# design.net
KiCad netlist of a schematic drawn in Altium Designer
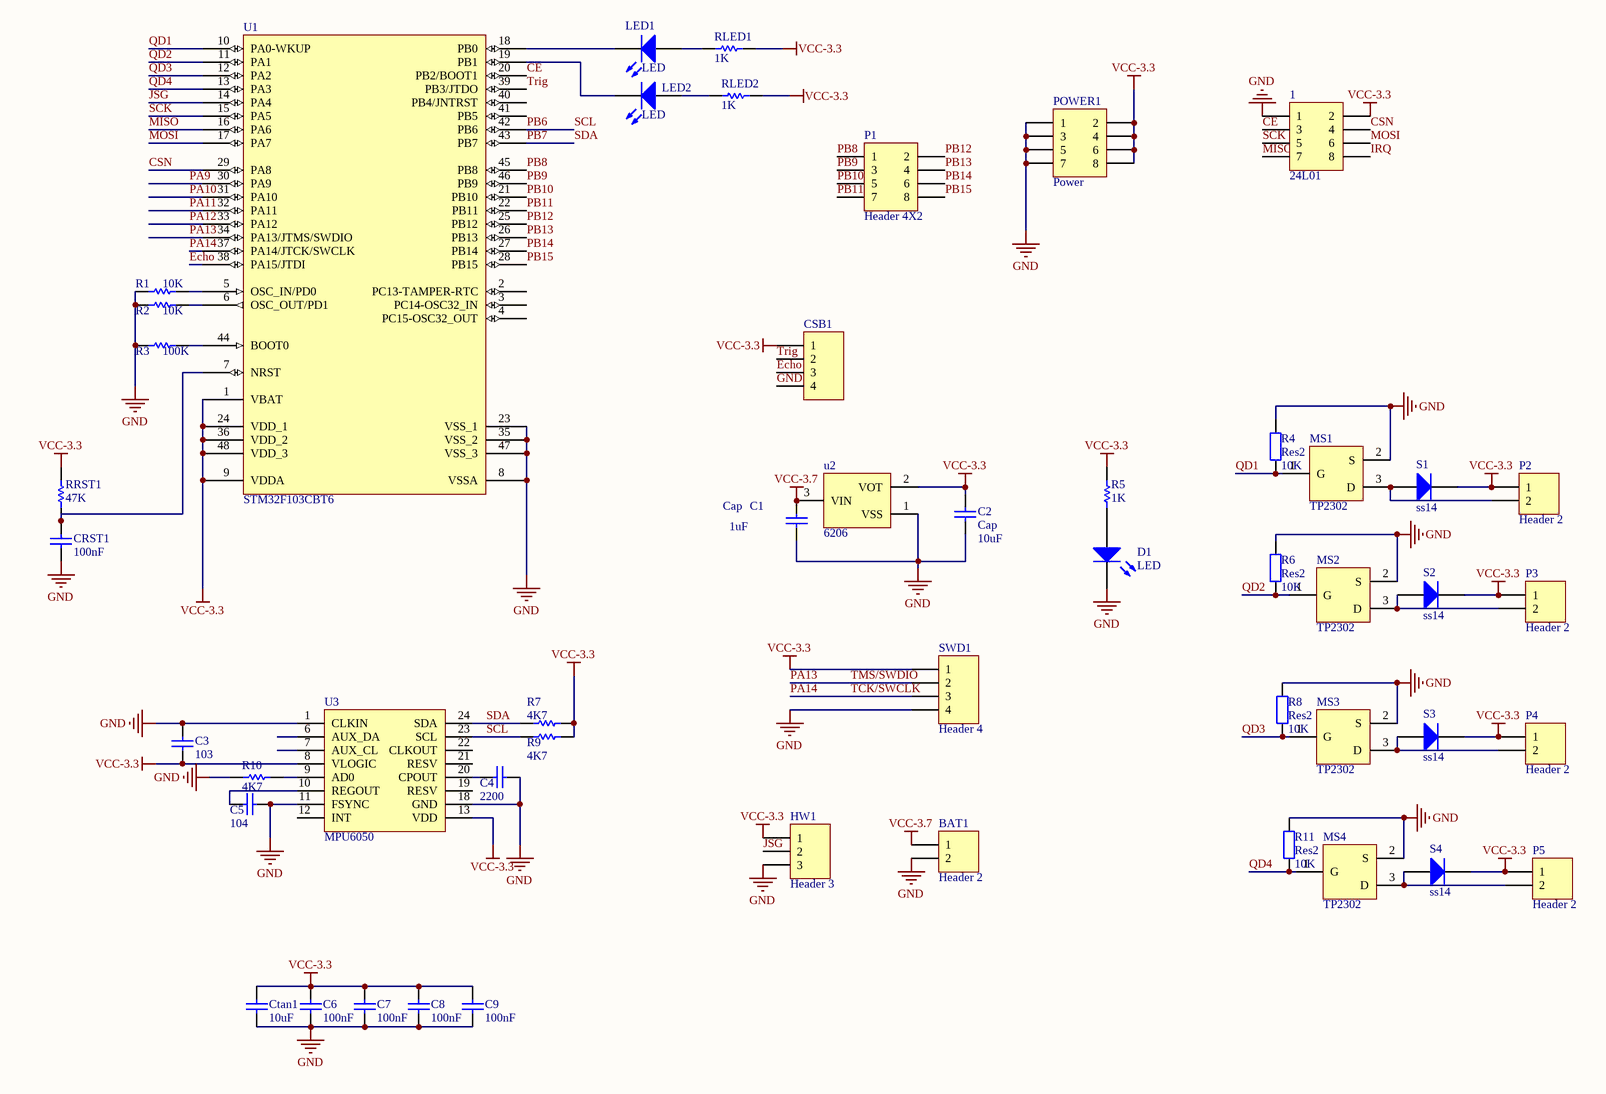
[diagram p0: 比赛飞控.SchDoc]

(export (version "E")
  (design (tool "Eeschema 10.0.6"))
  (components
    (comp (ref "1")
      (value "24L01")
      (footprint "HDR2X4")
      (description "Header, 4-Pin, Dual row")
      (fields (field (name "PUBLISHER") "Altium Limited"))
      (libsource (lib "Miscellaneous Connectors") (part "Header 4X2"))
    )
    (comp (ref "BAT1")
      (value "Header 2")
      (footprint "HDR1X2")
      (description "Header, 2-Pin")
      (fields (field (name "PUBLISHER") "Altium Limited"))
      (libsource (lib "Miscellaneous Connectors") (part "Header 2"))
    )
    (comp (ref "C1")
      (value "Cap")
      (footprint "0805")
      (description "Capacitor")
      (fields (field (name "ALTIUM_VALUE") "1uF") (field (name "PUBLISHER") "Altium Limited"))
      (libsource (lib "Miscellaneous Devices") (part "Cap"))
    )
    (comp (ref "C2")
      (value "Cap")
      (footprint "0805")
      (description "Capacitor")
      (fields (field (name "ALTIUM_VALUE") "10uF") (field (name "PUBLISHER") "Altium Limited"))
      (libsource (lib "Miscellaneous Devices") (part "Cap"))
    )
    (comp (ref "C3")
      (value "103")
      (footprint "0805")
      (description "Capacitor")
      (fields (field (name "Comment") "Cap") (field (name "PUBLISHER") "Altium Limited"))
      (libsource (lib "Miscellaneous Devices") (part "Cap"))
    )
    (comp (ref "C4")
      (value "2200")
      (footprint "0805")
      (description "Capacitor")
      (fields (field (name "Comment") "Cap") (field (name "PUBLISHER") "Altium Limited"))
      (libsource (lib "Miscellaneous Devices") (part "Cap"))
    )
    (comp (ref "C5")
      (value "104")
      (footprint "0805")
      (description "Capacitor")
      (fields (field (name "Comment") "Cap") (field (name "PUBLISHER") "Altium Limited"))
      (libsource (lib "Miscellaneous Devices") (part "Cap"))
    )
    (comp (ref "C6")
      (value "100nF")
      (footprint "0805")
      (description "Capacitor")
      (fields (field (name "Comment") "Cap") (field (name "PUBLISHER") "Altium Limited"))
      (libsource (lib "Miscellaneous Devices") (part "Cap"))
    )
    (comp (ref "C7")
      (value "100nF")
      (footprint "0805")
      (description "Capacitor")
      (fields (field (name "Comment") "Cap") (field (name "PUBLISHER") "Altium Limited"))
      (libsource (lib "Miscellaneous Devices") (part "Cap"))
    )
    (comp (ref "C8")
      (value "100nF")
      (footprint "0805")
      (description "Capacitor")
      (fields (field (name "Comment") "Cap") (field (name "PUBLISHER") "Altium Limited"))
      (libsource (lib "Miscellaneous Devices") (part "Cap"))
    )
    (comp (ref "C9")
      (value "100nF")
      (footprint "0805")
      (description "Capacitor")
      (fields (field (name "Comment") "Cap") (field (name "PUBLISHER") "Altium Limited"))
      (libsource (lib "Miscellaneous Devices") (part "Cap"))
    )
    (comp (ref "CRST1")
      (value "100nF")
      (footprint "0805")
      (description "Capacitor")
      (fields (field (name "Comment") "Cap") (field (name "PUBLISHER") "Altium Limited"))
      (libsource (lib "Miscellaneous Devices") (part "Cap"))
    )
    (comp (ref "CSB1")
      (value "~")
      (footprint "HDR1X4")
      (description "Header, 4-Pin")
      (fields (field (name "PUBLISHER") "Altium Limited"))
      (libsource (lib "Miscellaneous Connectors") (part "Header 4"))
    )
    (comp (ref "Ctan1")
      (value "10uF")
      (footprint "0805")
      (description "Capacitor")
      (fields (field (name "Comment") "Cap") (field (name "PUBLISHER") "Altium Limited"))
      (libsource (lib "Miscellaneous Devices") (part "Cap"))
    )
    (comp (ref "D1")
      (value "LED")
      (footprint "0805")
      (description "Typical BLUE SiC LED")
      (fields (field (name "PUBLISHER") "Altium Limited"))
      (libsource (lib "Miscellaneous Devices") (part "LED3"))
    )
    (comp (ref "HW1")
      (value "Header 3")
      (footprint "HDR1X3")
      (description "Header, 3-Pin")
      (fields (field (name "PUBLISHER") "Altium Limited"))
      (libsource (lib "Miscellaneous Connectors") (part "Header 3"))
    )
    (comp (ref "LED1")
      (value "LED")
      (footprint "0805")
      (description "Typical BLUE SiC LED")
      (fields (field (name "PUBLISHER") "Altium Limited"))
      (libsource (lib "Miscellaneous Devices") (part "LED3"))
    )
    (comp (ref "LED2")
      (value "LED")
      (footprint "0805")
      (description "Typical BLUE SiC LED")
      (fields (field (name "PUBLISHER") "Altium Limited"))
      (libsource (lib "Miscellaneous Devices") (part "LED3"))
    )
    (comp (ref "MS1") (value "TP2302") (footprint "SOT-23") (libsource (lib "TP2302") (part "TP2302")))
    (comp (ref "MS2") (value "TP2302") (footprint "SOT-23") (libsource (lib "TP2302") (part "TP2302")))
    (comp (ref "MS3") (value "TP2302") (footprint "SOT-23") (libsource (lib "TP2302") (part "TP2302")))
    (comp (ref "MS4") (value "TP2302") (footprint "SOT-23") (libsource (lib "TP2302") (part "TP2302")))
    (comp (ref "P1")
      (value "Header 4X2")
      (footprint "HDR2X4")
      (description "Header, 4-Pin, Dual row")
      (fields (field (name "PUBLISHER") "Altium Limited"))
      (libsource (lib "Miscellaneous Connectors") (part "Header 4X2"))
    )
    (comp (ref "P2")
      (value "Header 2")
      (footprint "HDR1X2")
      (description "Header, 2-Pin")
      (fields (field (name "PUBLISHER") "Altium Limited"))
      (libsource (lib "Miscellaneous Connectors") (part "Header 2"))
    )
    (comp (ref "P3")
      (value "Header 2")
      (footprint "HDR1X2")
      (description "Header, 2-Pin")
      (fields (field (name "PUBLISHER") "Altium Limited"))
      (libsource (lib "Miscellaneous Connectors") (part "Header 2"))
    )
    (comp (ref "P4")
      (value "Header 2")
      (footprint "HDR1X2")
      (description "Header, 2-Pin")
      (fields (field (name "PUBLISHER") "Altium Limited"))
      (libsource (lib "Miscellaneous Connectors") (part "Header 2"))
    )
    (comp (ref "P5")
      (value "Header 2")
      (footprint "HDR1X2")
      (description "Header, 2-Pin")
      (fields (field (name "PUBLISHER") "Altium Limited"))
      (libsource (lib "Miscellaneous Connectors") (part "Header 2"))
    )
    (comp (ref "POWER1")
      (value "Power")
      (footprint "HDR2X4")
      (description "Header, 4-Pin, Dual row")
      (fields (field (name "PUBLISHER") "Altium Limited"))
      (libsource (lib "Miscellaneous Connectors") (part "Header 4X2"))
    )
    (comp (ref "R1")
      (value "10K")
      (footprint "0603")
      (description "Resistor")
      (fields (field (name "Comment") "Res1") (field (name "PUBLISHER") "Altium Limited"))
      (libsource (lib "Miscellaneous Devices") (part "Res1"))
    )
    (comp (ref "R2")
      (value "10K")
      (footprint "0603")
      (description "Resistor")
      (fields (field (name "Comment") "Res1") (field (name "PUBLISHER") "Altium Limited"))
      (libsource (lib "Miscellaneous Devices") (part "Res1"))
    )
    (comp (ref "R3")
      (value "100K")
      (footprint "0603")
      (description "Resistor")
      (fields (field (name "Comment") "Res1") (field (name "PUBLISHER") "Altium Limited"))
      (libsource (lib "Miscellaneous Devices") (part "Res1"))
    )
    (comp (ref "R4")
      (value "Res2")
      (footprint "0805")
      (description "Resistor")
      (fields (field (name "ALTIUM_VALUE") "10K") (field (name "PUBLISHER") "Altium Limited"))
      (libsource (lib "Miscellaneous Devices") (part "Res2"))
    )
    (comp (ref "R5")
      (value "1K")
      (footprint "0805")
      (description "Resistor")
      (fields (field (name "Comment") "Res1") (field (name "PUBLISHER") "Altium Limited"))
      (libsource (lib "Miscellaneous Devices") (part "Res1"))
    )
    (comp (ref "R6")
      (value "Res2")
      (footprint "0805")
      (description "Resistor")
      (fields (field (name "ALTIUM_VALUE") "10K") (field (name "PUBLISHER") "Altium Limited"))
      (libsource (lib "Miscellaneous Devices") (part "Res2"))
    )
    (comp (ref "R7")
      (value "4K7")
      (footprint "0805")
      (description "Resistor")
      (fields (field (name "Comment") "Res1") (field (name "PUBLISHER") "Altium Limited"))
      (libsource (lib "Miscellaneous Devices") (part "Res1"))
    )
    (comp (ref "R8")
      (value "Res2")
      (footprint "0805")
      (description "Resistor")
      (fields (field (name "ALTIUM_VALUE") "10K") (field (name "PUBLISHER") "Altium Limited"))
      (libsource (lib "Miscellaneous Devices") (part "Res2"))
    )
    (comp (ref "R9")
      (value "4K7")
      (footprint "0805")
      (description "Resistor")
      (fields (field (name "Comment") "Res1") (field (name "PUBLISHER") "Altium Limited"))
      (libsource (lib "Miscellaneous Devices") (part "Res1"))
    )
    (comp (ref "R10")
      (value "4K7")
      (footprint "0805")
      (description "Resistor")
      (fields (field (name "Comment") "Res1") (field (name "PUBLISHER") "Altium Limited"))
      (libsource (lib "Miscellaneous Devices") (part "Res1"))
    )
    (comp (ref "R11")
      (value "Res2")
      (footprint "0805")
      (description "Resistor")
      (fields (field (name "ALTIUM_VALUE") "10K") (field (name "PUBLISHER") "Altium Limited"))
      (libsource (lib "Miscellaneous Devices") (part "Res2"))
    )
    (comp (ref "RLED1")
      (value "1K")
      (footprint "0805")
      (description "Resistor")
      (fields (field (name "Comment") "Res1") (field (name "PUBLISHER") "Altium Limited"))
      (libsource (lib "Miscellaneous Devices") (part "Res1"))
    )
    (comp (ref "RLED2")
      (value "1K")
      (footprint "0805")
      (description "Resistor")
      (fields (field (name "Comment") "Res1") (field (name "PUBLISHER") "Altium Limited"))
      (libsource (lib "Miscellaneous Devices") (part "Res1"))
    )
    (comp (ref "RRST1")
      (value "47K")
      (footprint "0805")
      (description "Resistor")
      (fields (field (name "Comment") "Res1") (field (name "PUBLISHER") "Altium Limited"))
      (libsource (lib "Miscellaneous Devices") (part "Res1"))
    )
    (comp (ref "S1")
      (value "ss14")
      (footprint "SOD-323")
      (description "3 Amp General Purpose Rectifier")
      (fields (field (name "PUBLISHER") "Altium Limited"))
      (libsource (lib "Miscellaneous Devices") (part "Diode 1N5406"))
    )
    (comp (ref "S2")
      (value "ss14")
      (footprint "SOD-323")
      (description "3 Amp General Purpose Rectifier")
      (fields (field (name "PUBLISHER") "Altium Limited"))
      (libsource (lib "Miscellaneous Devices") (part "Diode 1N5406"))
    )
    (comp (ref "S3")
      (value "ss14")
      (footprint "SOD-323")
      (description "3 Amp General Purpose Rectifier")
      (fields (field (name "PUBLISHER") "Altium Limited"))
      (libsource (lib "Miscellaneous Devices") (part "Diode 1N5406"))
    )
    (comp (ref "S4")
      (value "ss14")
      (footprint "SOD-323")
      (description "3 Amp General Purpose Rectifier")
      (fields (field (name "PUBLISHER") "Altium Limited"))
      (libsource (lib "Miscellaneous Devices") (part "Diode 1N5406"))
    )
    (comp (ref "SWD1")
      (value "Header 4")
      (footprint "HDR1X4")
      (description "Header, 4-Pin")
      (fields (field (name "PUBLISHER") "Altium Limited"))
      (libsource (lib "Miscellaneous Connectors") (part "Header 4"))
    )
    (comp (ref "U1")
      (value "STM32F103CBT6")
      (footprint "LQFP48_N")
      (description "STM32 ARM-based 32-bit MCU with 128 Kbytes Flash, 48-pin LQFP, Industrial Temperature")
      (fields (field (name "PUBLISHER") "Altium Limited"))
      (libsource (lib "ST Microcontroller 32-Bit STM32") (part "STM32F103CBT6"))
    )
    (comp (ref "u2") (value "6206") (footprint "SOT346-3AN") (libsource (lib "6206") (part "6206")))
    (comp (ref "U3")
      (value "MPU6050")
      (footprint "QFN-24")
      (description "Hex-Axis Sensor")
      (libsource (lib "My") (part "MPU6050"))
    )
  )
  (nets
    (net (code "1") (name "/CE") (class "Default")
      (node (ref "1") (pin "3") (pinfunction "3_3") (pintype "passive"))
      (node (ref "U1") (pin "20") (pinfunction "PB2/BOOT1_20") (pintype "bidirectional"))
    )
    (net (code "2") (name "/CSN") (class "Default")
      (node (ref "1") (pin "4") (pinfunction "4_4") (pintype "passive"))
      (node (ref "U1") (pin "29") (pinfunction "PA8_29") (pintype "bidirectional"))
    )
    (net (code "3") (name "/Echo") (class "Default")
      (node (ref "CSB1") (pin "3") (pinfunction "3_3") (pintype "passive"))
      (node (ref "U1") (pin "38") (pinfunction "PA15/JTDI_38") (pintype "bidirectional"))
    )
    (net (code "4") (name "/IRQ") (class "Default")
      (node (ref "1") (pin "8") (pinfunction "8_8") (pintype "passive"))
    )
    (net (code "5") (name "/JSG") (class "Default")
      (node (ref "HW1") (pin "2") (pinfunction "2_2") (pintype "passive"))
      (node (ref "U1") (pin "14") (pinfunction "PA4_14") (pintype "bidirectional"))
    )
    (net (code "6") (name "/MISO") (class "Default")
      (node (ref "1") (pin "7") (pinfunction "7_7") (pintype "passive"))
      (node (ref "U1") (pin "16") (pinfunction "PA6_16") (pintype "bidirectional"))
    )
    (net (code "7") (name "/MOSI") (class "Default")
      (node (ref "1") (pin "6") (pinfunction "6_6") (pintype "passive"))
      (node (ref "U1") (pin "17") (pinfunction "PA7_17") (pintype "bidirectional"))
    )
    (net (code "8") (name "/PA9") (class "Default")
      (node (ref "U1") (pin "30") (pinfunction "PA9_30") (pintype "bidirectional"))
    )
    (net (code "9") (name "/PA10") (class "Default")
      (node (ref "U1") (pin "31") (pinfunction "PA10_31") (pintype "bidirectional"))
    )
    (net (code "10") (name "/PA11") (class "Default")
      (node (ref "U1") (pin "32") (pinfunction "PA11_32") (pintype "bidirectional"))
    )
    (net (code "11") (name "/PA12") (class "Default")
      (node (ref "U1") (pin "33") (pinfunction "PA12_33") (pintype "bidirectional"))
    )
    (net (code "12") (name "/PA13") (class "Default")
      (node (ref "SWD1") (pin "2") (pinfunction "2_2") (pintype "passive"))
      (node (ref "U1") (pin "34") (pinfunction "PA13/JTMS/SWDIO_34") (pintype "bidirectional"))
    )
    (net (code "13") (name "/PA14") (class "Default")
      (node (ref "SWD1") (pin "3") (pinfunction "3_3") (pintype "passive"))
      (node (ref "U1") (pin "37") (pinfunction "PA14/JTCK/SWCLK_37") (pintype "bidirectional"))
    )
    (net (code "14") (name "/PB6") (class "Default")
      (node (ref "R9") (pin "1") (pinfunction "1_1") (pintype "passive"))
      (node (ref "U1") (pin "42") (pinfunction "PB6_42") (pintype "bidirectional"))
      (node (ref "U3") (pin "23") (pinfunction "SCL_23") (pintype "passive"))
    )
    (net (code "15") (name "/PB7") (class "Default")
      (node (ref "R7") (pin "1") (pinfunction "1_1") (pintype "passive"))
      (node (ref "U1") (pin "43") (pinfunction "PB7_43") (pintype "bidirectional"))
      (node (ref "U3") (pin "24") (pinfunction "SDA_24") (pintype "passive"))
    )
    (net (code "16") (name "/PB8") (class "Default")
      (node (ref "P1") (pin "1") (pinfunction "1_1") (pintype "passive"))
      (node (ref "U1") (pin "45") (pinfunction "PB8_45") (pintype "bidirectional"))
    )
    (net (code "17") (name "/PB9") (class "Default")
      (node (ref "P1") (pin "3") (pinfunction "3_3") (pintype "passive"))
      (node (ref "U1") (pin "46") (pinfunction "PB9_46") (pintype "bidirectional"))
    )
    (net (code "18") (name "/PB10") (class "Default")
      (node (ref "P1") (pin "5") (pinfunction "5_5") (pintype "passive"))
      (node (ref "U1") (pin "21") (pinfunction "PB10_21") (pintype "bidirectional"))
    )
    (net (code "19") (name "/PB11") (class "Default")
      (node (ref "P1") (pin "7") (pinfunction "7_7") (pintype "passive"))
      (node (ref "U1") (pin "22") (pinfunction "PB11_22") (pintype "bidirectional"))
    )
    (net (code "20") (name "/PB12") (class "Default")
      (node (ref "P1") (pin "2") (pinfunction "2_2") (pintype "passive"))
      (node (ref "U1") (pin "25") (pinfunction "PB12_25") (pintype "bidirectional"))
    )
    (net (code "21") (name "/PB13") (class "Default")
      (node (ref "P1") (pin "4") (pinfunction "4_4") (pintype "passive"))
      (node (ref "U1") (pin "26") (pinfunction "PB13_26") (pintype "bidirectional"))
    )
    (net (code "22") (name "/PB14") (class "Default")
      (node (ref "P1") (pin "6") (pinfunction "6_6") (pintype "passive"))
      (node (ref "U1") (pin "27") (pinfunction "PB14_27") (pintype "bidirectional"))
    )
    (net (code "23") (name "/PB15") (class "Default")
      (node (ref "P1") (pin "8") (pinfunction "8_8") (pintype "passive"))
      (node (ref "U1") (pin "28") (pinfunction "PB15_28") (pintype "bidirectional"))
    )
    (net (code "24") (name "/QD1") (class "Default")
      (node (ref "MS1") (pin "1") (pinfunction "G_1") (pintype "passive"))
      (node (ref "R4") (pin "1") (pinfunction "1_1") (pintype "passive"))
      (node (ref "U1") (pin "10") (pinfunction "PA0-WKUP_10") (pintype "bidirectional"))
    )
    (net (code "25") (name "/QD2") (class "Default")
      (node (ref "MS2") (pin "1") (pinfunction "G_1") (pintype "passive"))
      (node (ref "R6") (pin "1") (pinfunction "1_1") (pintype "passive"))
      (node (ref "U1") (pin "11") (pinfunction "PA1_11") (pintype "bidirectional"))
    )
    (net (code "26") (name "/QD3") (class "Default")
      (node (ref "MS3") (pin "1") (pinfunction "G_1") (pintype "passive"))
      (node (ref "R8") (pin "1") (pinfunction "1_1") (pintype "passive"))
      (node (ref "U1") (pin "12") (pinfunction "PA2_12") (pintype "bidirectional"))
    )
    (net (code "27") (name "/QD4") (class "Default")
      (node (ref "MS4") (pin "1") (pinfunction "G_1") (pintype "passive"))
      (node (ref "R11") (pin "1") (pinfunction "1_1") (pintype "passive"))
      (node (ref "U1") (pin "13") (pinfunction "PA3_13") (pintype "bidirectional"))
    )
    (net (code "28") (name "/SCK") (class "Default")
      (node (ref "1") (pin "5") (pinfunction "5_5") (pintype "passive"))
      (node (ref "U1") (pin "15") (pinfunction "PA5_15") (pintype "bidirectional"))
    )
    (net (code "29") (name "/Trig") (class "Default")
      (node (ref "CSB1") (pin "2") (pinfunction "2_2") (pintype "passive"))
      (node (ref "U1") (pin "39") (pinfunction "PB3/JTDO_39") (pintype "bidirectional"))
    )
    (net (code "30") (name "GND") (class "Default")
      (node (ref "1") (pin "1") (pinfunction "1_1") (pintype "passive"))
      (node (ref "BAT1") (pin "2") (pinfunction "2_2") (pintype "passive"))
      (node (ref "C1") (pin "2") (pinfunction "2_2") (pintype "passive"))
      (node (ref "C2") (pin "2") (pinfunction "2_2") (pintype "passive"))
      (node (ref "C3") (pin "2") (pinfunction "2_2") (pintype "passive"))
      (node (ref "C4") (pin "2") (pinfunction "2_2") (pintype "passive"))
      (node (ref "C5") (pin "1") (pinfunction "1_1") (pintype "passive"))
      (node (ref "C6") (pin "1") (pinfunction "1_1") (pintype "passive"))
      (node (ref "C7") (pin "1") (pinfunction "1_1") (pintype "passive"))
      (node (ref "C8") (pin "1") (pinfunction "1_1") (pintype "passive"))
      (node (ref "C9") (pin "1") (pinfunction "1_1") (pintype "passive"))
      (node (ref "CRST1") (pin "2") (pinfunction "2_2") (pintype "passive"))
      (node (ref "CSB1") (pin "4") (pinfunction "4_4") (pintype "passive"))
      (node (ref "Ctan1") (pin "1") (pinfunction "1_1") (pintype "passive"))
      (node (ref "D1") (pin "2") (pinfunction "K_2") (pintype "passive"))
      (node (ref "HW1") (pin "3") (pinfunction "3_3") (pintype "passive"))
      (node (ref "MS1") (pin "2") (pinfunction "S_2") (pintype "passive"))
      (node (ref "MS2") (pin "2") (pinfunction "S_2") (pintype "passive"))
      (node (ref "MS3") (pin "2") (pinfunction "S_2") (pintype "passive"))
      (node (ref "MS4") (pin "2") (pinfunction "S_2") (pintype "passive"))
      (node (ref "POWER1") (pin "1") (pinfunction "1_1") (pintype "passive"))
      (node (ref "POWER1") (pin "3") (pinfunction "3_3") (pintype "passive"))
      (node (ref "POWER1") (pin "5") (pinfunction "5_5") (pintype "passive"))
      (node (ref "POWER1") (pin "7") (pinfunction "7_7") (pintype "passive"))
      (node (ref "R1") (pin "1") (pinfunction "1_1") (pintype "passive"))
      (node (ref "R10") (pin "1") (pinfunction "1_1") (pintype "passive"))
      (node (ref "R11") (pin "2") (pinfunction "2_2") (pintype "passive"))
      (node (ref "R2") (pin "1") (pinfunction "1_1") (pintype "passive"))
      (node (ref "R3") (pin "1") (pinfunction "1_1") (pintype "passive"))
      (node (ref "R4") (pin "2") (pinfunction "2_2") (pintype "passive"))
      (node (ref "R6") (pin "2") (pinfunction "2_2") (pintype "passive"))
      (node (ref "R8") (pin "2") (pinfunction "2_2") (pintype "passive"))
      (node (ref "SWD1") (pin "4") (pinfunction "4_4") (pintype "passive"))
      (node (ref "U1") (pin "23") (pinfunction "VSS_1_23") (pintype "power_in"))
      (node (ref "U1") (pin "35") (pinfunction "VSS_2_35") (pintype "power_in"))
      (node (ref "U1") (pin "47") (pinfunction "VSS_3_47") (pintype "power_in"))
      (node (ref "U1") (pin "8") (pinfunction "VSSA_8") (pintype "power_in"))
      (node (ref "U3") (pin "1") (pinfunction "CLKIN_1") (pintype "passive"))
      (node (ref "U3") (pin "11") (pinfunction "FSYNC_11") (pintype "passive"))
      (node (ref "U3") (pin "18") (pinfunction "GND_18") (pintype "passive"))
      (node (ref "u2") (pin "1") (pinfunction "VSS_1") (pintype "passive"))
    )
    (net (code "31") (name "Net-(D1-A)") (class "Default")
      (node (ref "D1") (pin "1") (pinfunction "A_1") (pintype "passive"))
      (node (ref "R5") (pin "1") (pinfunction "1_1") (pintype "passive"))
    )
    (net (code "32") (name "Net-(LED1-A)") (class "Default")
      (node (ref "LED1") (pin "1") (pinfunction "A_1") (pintype "passive"))
      (node (ref "RLED1") (pin "2") (pinfunction "2_2") (pintype "passive"))
    )
    (net (code "33") (name "Net-(LED1-K)") (class "Default")
      (node (ref "LED1") (pin "2") (pinfunction "K_2") (pintype "passive"))
      (node (ref "U1") (pin "18") (pinfunction "PB0_18") (pintype "bidirectional"))
    )
    (net (code "34") (name "Net-(LED2-A)") (class "Default")
      (node (ref "LED2") (pin "1") (pinfunction "A_1") (pintype "passive"))
      (node (ref "RLED2") (pin "2") (pinfunction "2_2") (pintype "passive"))
    )
    (net (code "35") (name "Net-(LED2-K)") (class "Default")
      (node (ref "LED2") (pin "2") (pinfunction "K_2") (pintype "passive"))
      (node (ref "U1") (pin "19") (pinfunction "PB1_19") (pintype "bidirectional"))
    )
    (net (code "36") (name "Net-(MS1-D)") (class "Default")
      (node (ref "MS1") (pin "3") (pinfunction "D_3") (pintype "passive"))
      (node (ref "P2") (pin "2") (pinfunction "2_2") (pintype "passive"))
      (node (ref "S1") (pin "1") (pinfunction "A_1") (pintype "passive"))
    )
    (net (code "37") (name "Net-(MS2-D)") (class "Default")
      (node (ref "MS2") (pin "3") (pinfunction "D_3") (pintype "passive"))
      (node (ref "P3") (pin "2") (pinfunction "2_2") (pintype "passive"))
      (node (ref "S2") (pin "1") (pinfunction "A_1") (pintype "passive"))
    )
    (net (code "38") (name "Net-(MS3-D)") (class "Default")
      (node (ref "MS3") (pin "3") (pinfunction "D_3") (pintype "passive"))
      (node (ref "P4") (pin "2") (pinfunction "2_2") (pintype "passive"))
      (node (ref "S3") (pin "1") (pinfunction "A_1") (pintype "passive"))
    )
    (net (code "39") (name "Net-(MS4-D)") (class "Default")
      (node (ref "MS4") (pin "3") (pinfunction "D_3") (pintype "passive"))
      (node (ref "P5") (pin "2") (pinfunction "2_2") (pintype "passive"))
      (node (ref "S4") (pin "1") (pinfunction "A_1") (pintype "passive"))
    )
    (net (code "40") (name "Net-(U1-BOOT0)") (class "Default")
      (node (ref "R3") (pin "2") (pinfunction "2_2") (pintype "passive"))
      (node (ref "U1") (pin "44") (pinfunction "BOOT0_44") (pintype "input"))
    )
    (net (code "41") (name "Net-(U1-NRST)") (class "Default")
      (node (ref "CRST1") (pin "1") (pinfunction "1_1") (pintype "passive"))
      (node (ref "RRST1") (pin "1") (pinfunction "1_1") (pintype "passive"))
      (node (ref "U1") (pin "7") (pinfunction "NRST_7") (pintype "bidirectional"))
    )
    (net (code "42") (name "Net-(U1-OSC_IN{slash}PD0)") (class "Default")
      (node (ref "R1") (pin "2") (pinfunction "2_2") (pintype "passive"))
      (node (ref "U1") (pin "5") (pinfunction "OSC_IN/PD0_5") (pintype "input"))
    )
    (net (code "43") (name "Net-(U1-OSC_OUT{slash}PD1)") (class "Default")
      (node (ref "R2") (pin "2") (pinfunction "2_2") (pintype "passive"))
      (node (ref "U1") (pin "6") (pinfunction "OSC_OUT/PD1_6") (pintype "output"))
    )
    (net (code "44") (name "Net-(U3-AD0)") (class "Default")
      (node (ref "R10") (pin "2") (pinfunction "2_2") (pintype "passive"))
      (node (ref "U3") (pin "9") (pinfunction "AD0_9") (pintype "passive"))
    )
    (net (code "45") (name "Net-(U3-CPOUT)") (class "Default")
      (node (ref "C4") (pin "1") (pinfunction "1_1") (pintype "passive"))
      (node (ref "U3") (pin "20") (pinfunction "CPOUT_20") (pintype "passive"))
    )
    (net (code "46") (name "Net-(U3-REGOUT)") (class "Default")
      (node (ref "C5") (pin "2") (pinfunction "2_2") (pintype "passive"))
      (node (ref "U3") (pin "10") (pinfunction "REGOUT_10") (pintype "passive"))
    )
    (net (code "47") (name "VCC-3.3") (class "Default")
      (node (ref "1") (pin "2") (pinfunction "2_2") (pintype "passive"))
      (node (ref "C2") (pin "1") (pinfunction "1_1") (pintype "passive"))
      (node (ref "C3") (pin "1") (pinfunction "1_1") (pintype "passive"))
      (node (ref "C6") (pin "2") (pinfunction "2_2") (pintype "passive"))
      (node (ref "C7") (pin "2") (pinfunction "2_2") (pintype "passive"))
      (node (ref "C8") (pin "2") (pinfunction "2_2") (pintype "passive"))
      (node (ref "C9") (pin "2") (pinfunction "2_2") (pintype "passive"))
      (node (ref "CSB1") (pin "1") (pinfunction "1_1") (pintype "passive"))
      (node (ref "Ctan1") (pin "2") (pinfunction "2_2") (pintype "passive"))
      (node (ref "HW1") (pin "1") (pinfunction "1_1") (pintype "passive"))
      (node (ref "P2") (pin "1") (pinfunction "1_1") (pintype "passive"))
      (node (ref "P3") (pin "1") (pinfunction "1_1") (pintype "passive"))
      (node (ref "P4") (pin "1") (pinfunction "1_1") (pintype "passive"))
      (node (ref "P5") (pin "1") (pinfunction "1_1") (pintype "passive"))
      (node (ref "POWER1") (pin "2") (pinfunction "2_2") (pintype "passive"))
      (node (ref "POWER1") (pin "4") (pinfunction "4_4") (pintype "passive"))
      (node (ref "POWER1") (pin "6") (pinfunction "6_6") (pintype "passive"))
      (node (ref "POWER1") (pin "8") (pinfunction "8_8") (pintype "passive"))
      (node (ref "R5") (pin "2") (pinfunction "2_2") (pintype "passive"))
      (node (ref "R7") (pin "2") (pinfunction "2_2") (pintype "passive"))
      (node (ref "R9") (pin "2") (pinfunction "2_2") (pintype "passive"))
      (node (ref "RLED1") (pin "1") (pinfunction "1_1") (pintype "passive"))
      (node (ref "RLED2") (pin "1") (pinfunction "1_1") (pintype "passive"))
      (node (ref "RRST1") (pin "2") (pinfunction "2_2") (pintype "passive"))
      (node (ref "S1") (pin "2") (pinfunction "K_2") (pintype "passive"))
      (node (ref "S2") (pin "2") (pinfunction "K_2") (pintype "passive"))
      (node (ref "S3") (pin "2") (pinfunction "K_2") (pintype "passive"))
      (node (ref "S4") (pin "2") (pinfunction "K_2") (pintype "passive"))
      (node (ref "SWD1") (pin "1") (pinfunction "1_1") (pintype "passive"))
      (node (ref "U1") (pin "1") (pinfunction "VBAT_1") (pintype "power_in"))
      (node (ref "U1") (pin "24") (pinfunction "VDD_1_24") (pintype "power_in"))
      (node (ref "U1") (pin "36") (pinfunction "VDD_2_36") (pintype "power_in"))
      (node (ref "U1") (pin "48") (pinfunction "VDD_3_48") (pintype "power_in"))
      (node (ref "U1") (pin "9") (pinfunction "VDDA_9") (pintype "power_in"))
      (node (ref "U3") (pin "13") (pinfunction "VDD_13") (pintype "passive"))
      (node (ref "U3") (pin "8") (pinfunction "VLOGIC_8") (pintype "passive"))
      (node (ref "u2") (pin "2") (pinfunction "VOT_2") (pintype "passive"))
    )
    (net (code "48") (name "VCC-3.7") (class "Default")
      (node (ref "BAT1") (pin "1") (pinfunction "1_1") (pintype "passive"))
      (node (ref "C1") (pin "1") (pinfunction "1_1") (pintype "passive"))
      (node (ref "u2") (pin "3") (pinfunction "VIN_3") (pintype "passive"))
    )
    (net (code "49") (name "unconnected-(U1-PB4{slash}JNTRST-Pad40)") (class "Default")
      (node (ref "U1") (pin "40") (pinfunction "PB4/JNTRST_40") (pintype "bidirectional"))
    )
    (net (code "50") (name "unconnected-(U1-PB5-Pad41)") (class "Default")
      (node (ref "U1") (pin "41") (pinfunction "PB5_41") (pintype "bidirectional"))
    )
    (net (code "51") (name "unconnected-(U1-PC13-TAMPER-RTC-Pad2)") (class "Default")
      (node (ref "U1") (pin "2") (pinfunction "PC13-TAMPER-RTC_2") (pintype "bidirectional"))
    )
    (net (code "52") (name "unconnected-(U1-PC14-OSC32_IN-Pad3)") (class "Default")
      (node (ref "U1") (pin "3") (pinfunction "PC14-OSC32_IN_3") (pintype "bidirectional"))
    )
    (net (code "53") (name "unconnected-(U1-PC15-OSC32_OUT-Pad4)") (class "Default")
      (node (ref "U1") (pin "4") (pinfunction "PC15-OSC32_OUT_4") (pintype "bidirectional"))
    )
    (net (code "54") (name "unconnected-(U3-AUX_CL-Pad7)") (class "Default")
      (node (ref "U3") (pin "7") (pinfunction "AUX_CL_7") (pintype "passive"))
    )
    (net (code "55") (name "unconnected-(U3-AUX_DA-Pad6)") (class "Default")
      (node (ref "U3") (pin "6") (pinfunction "AUX_DA_6") (pintype "passive"))
    )
    (net (code "56") (name "unconnected-(U3-CLKOUT-Pad22)") (class "Default")
      (node (ref "U3") (pin "22") (pinfunction "CLKOUT_22") (pintype "passive"))
    )
    (net (code "57") (name "unconnected-(U3-INT-Pad12)") (class "Default")
      (node (ref "U3") (pin "12") (pinfunction "INT_12") (pintype "passive"))
    )
    (net (code "58") (name "unconnected-(U3-RESV-Pad19)") (class "Default")
      (node (ref "U3") (pin "19") (pinfunction "RESV_19") (pintype "passive"))
    )
    (net (code "59") (name "unconnected-(U3-RESV-Pad21)") (class "Default")
      (node (ref "U3") (pin "21") (pinfunction "RESV_21") (pintype "passive"))
    )
  )
)
